# Probe-Scope_Power_v1_0.net
KiCad netlist of a schematic drawn in Altium Designer
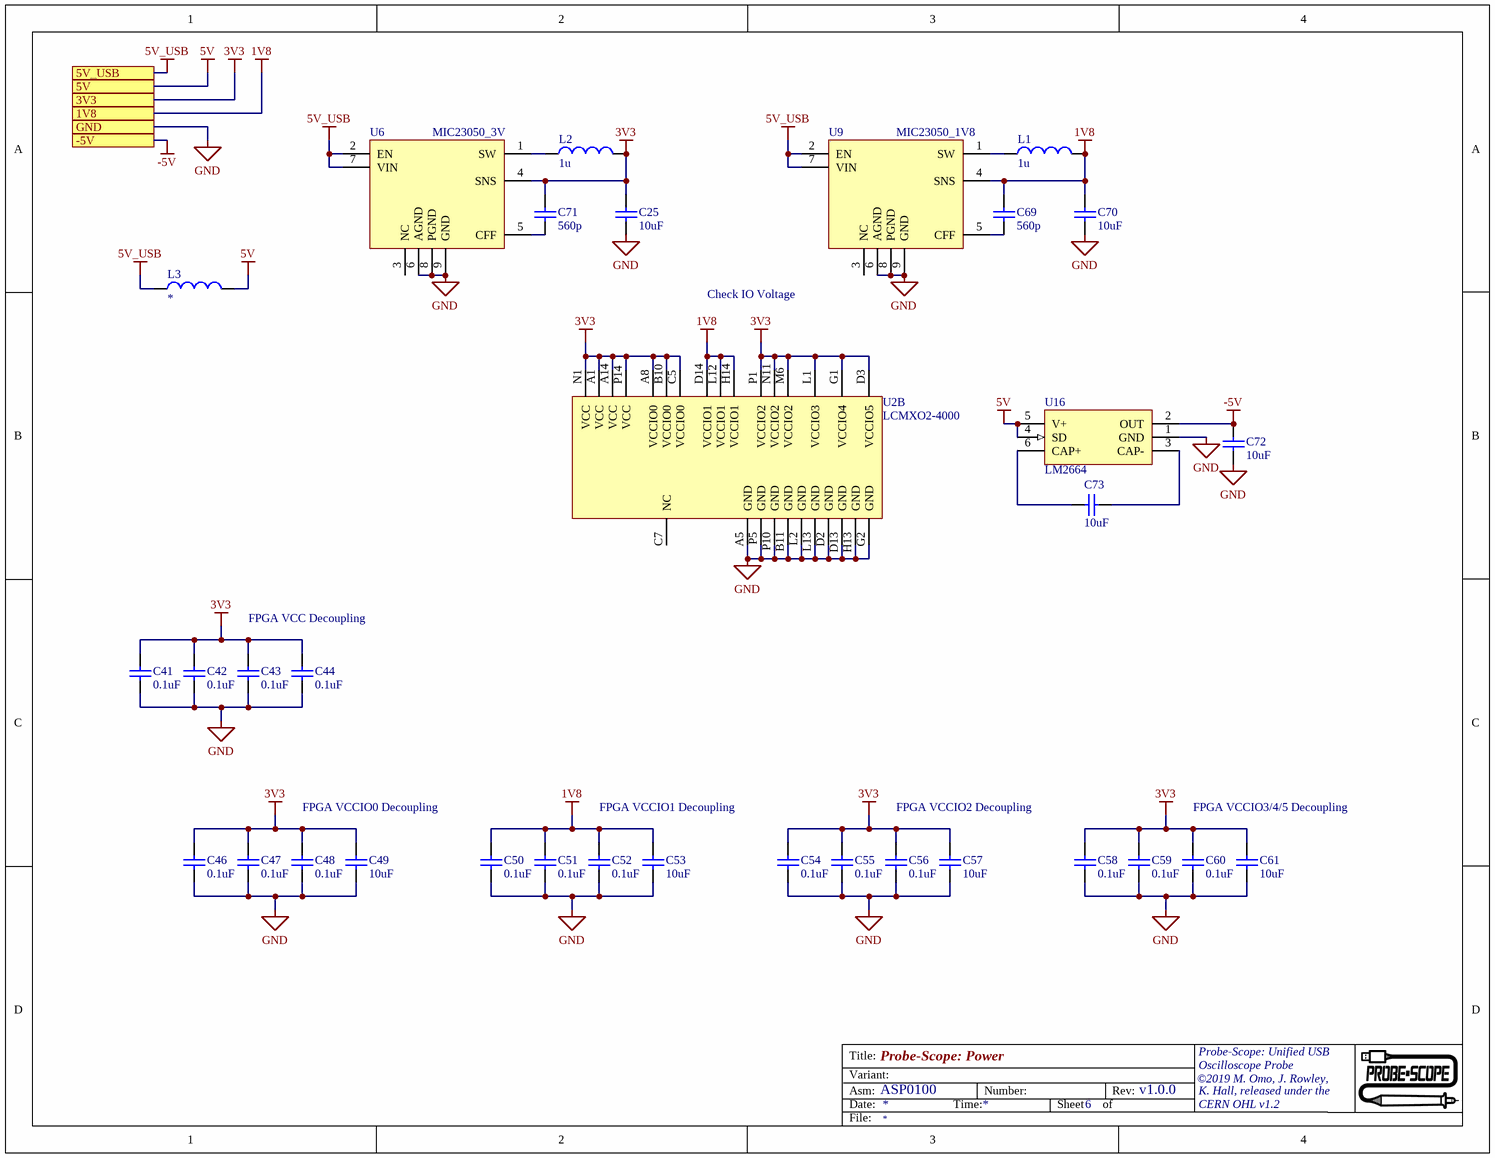
[diagram p0: Probe-Scope Power v1.0.SchDoc]

(export (version "E")
  (design (tool "Eeschema 10.0.6"))
  (components
    (comp (ref "C25")
      (value "10uF")
      (footprint "0603(1608)")
      (fields
        (field (name "MANF") "Samsung Electro-Mechanics")
        (field (name "TOLERANCE") "20")
        (field (name "VOLTAGE") "25")
        (field (name "MODIFIED BY") "sotterbacher")
        (field (name "APPROVED") "True")
      )
      (libsource (lib "MENG Database Library VPN") (part "Cap"))
    )
    (comp (ref "C41")
      (value "0.1uF")
      (footprint "0402(1005)")
      (fields
        (field (name "MANF") "Samsung Electro-Mechanics")
        (field (name "TOLERANCE") "10")
        (field (name "VOLTAGE") "6.3")
        (field (name "MODIFIED BY") "jrowley")
        (field (name "APPROVED") "False")
      )
      (libsource (lib "MENG Database Library VPN") (part "Cap"))
    )
    (comp (ref "C42")
      (value "0.1uF")
      (footprint "0402(1005)")
      (fields
        (field (name "MANF") "Samsung Electro-Mechanics")
        (field (name "TOLERANCE") "10")
        (field (name "VOLTAGE") "6.3")
        (field (name "MODIFIED BY") "jrowley")
        (field (name "APPROVED") "False")
      )
      (libsource (lib "MENG Database Library VPN") (part "Cap"))
    )
    (comp (ref "C43")
      (value "0.1uF")
      (footprint "0402(1005)")
      (fields
        (field (name "MANF") "Samsung Electro-Mechanics")
        (field (name "TOLERANCE") "10")
        (field (name "VOLTAGE") "6.3")
        (field (name "MODIFIED BY") "jrowley")
        (field (name "APPROVED") "False")
      )
      (libsource (lib "MENG Database Library VPN") (part "Cap"))
    )
    (comp (ref "C44")
      (value "0.1uF")
      (footprint "0402(1005)")
      (fields
        (field (name "MANF") "Samsung Electro-Mechanics")
        (field (name "TOLERANCE") "10")
        (field (name "VOLTAGE") "6.3")
        (field (name "MODIFIED BY") "jrowley")
        (field (name "APPROVED") "False")
      )
      (libsource (lib "MENG Database Library VPN") (part "Cap"))
    )
    (comp (ref "C46")
      (value "0.1uF")
      (footprint "0402(1005)")
      (fields
        (field (name "MANF") "Samsung Electro-Mechanics")
        (field (name "TOLERANCE") "10")
        (field (name "VOLTAGE") "6.3")
        (field (name "MODIFIED BY") "jrowley")
        (field (name "APPROVED") "False")
      )
      (libsource (lib "MENG Database Library VPN") (part "Cap"))
    )
    (comp (ref "C47")
      (value "0.1uF")
      (footprint "0402(1005)")
      (fields
        (field (name "MANF") "Samsung Electro-Mechanics")
        (field (name "TOLERANCE") "10")
        (field (name "VOLTAGE") "6.3")
        (field (name "MODIFIED BY") "jrowley")
        (field (name "APPROVED") "False")
      )
      (libsource (lib "MENG Database Library VPN") (part "Cap"))
    )
    (comp (ref "C48")
      (value "0.1uF")
      (footprint "0402(1005)")
      (fields
        (field (name "MANF") "Samsung Electro-Mechanics")
        (field (name "TOLERANCE") "10")
        (field (name "VOLTAGE") "6.3")
        (field (name "MODIFIED BY") "jrowley")
        (field (name "APPROVED") "False")
      )
      (libsource (lib "MENG Database Library VPN") (part "Cap"))
    )
    (comp (ref "C49")
      (value "10uF")
      (footprint "0603(1608)")
      (fields
        (field (name "MANF") "Samsung Electro-Mechanics")
        (field (name "TOLERANCE") "20")
        (field (name "VOLTAGE") "25")
        (field (name "MODIFIED BY") "sotterbacher")
        (field (name "APPROVED") "True")
      )
      (libsource (lib "MENG Database Library VPN") (part "Cap"))
    )
    (comp (ref "C50")
      (value "0.1uF")
      (footprint "0402(1005)")
      (fields
        (field (name "MANF") "Samsung Electro-Mechanics")
        (field (name "TOLERANCE") "10")
        (field (name "VOLTAGE") "6.3")
        (field (name "MODIFIED BY") "jrowley")
        (field (name "APPROVED") "False")
      )
      (libsource (lib "MENG Database Library VPN") (part "Cap"))
    )
    (comp (ref "C51")
      (value "0.1uF")
      (footprint "0402(1005)")
      (fields
        (field (name "MANF") "Samsung Electro-Mechanics")
        (field (name "TOLERANCE") "10")
        (field (name "VOLTAGE") "6.3")
        (field (name "MODIFIED BY") "jrowley")
        (field (name "APPROVED") "False")
      )
      (libsource (lib "MENG Database Library VPN") (part "Cap"))
    )
    (comp (ref "C52")
      (value "0.1uF")
      (footprint "0402(1005)")
      (fields
        (field (name "MANF") "Samsung Electro-Mechanics")
        (field (name "TOLERANCE") "10")
        (field (name "VOLTAGE") "6.3")
        (field (name "MODIFIED BY") "jrowley")
        (field (name "APPROVED") "False")
      )
      (libsource (lib "MENG Database Library VPN") (part "Cap"))
    )
    (comp (ref "C53")
      (value "10uF")
      (footprint "0603(1608)")
      (fields
        (field (name "MANF") "Samsung Electro-Mechanics")
        (field (name "TOLERANCE") "20")
        (field (name "VOLTAGE") "25")
        (field (name "MODIFIED BY") "sotterbacher")
        (field (name "APPROVED") "True")
      )
      (libsource (lib "MENG Database Library VPN") (part "Cap"))
    )
    (comp (ref "C54")
      (value "0.1uF")
      (footprint "0402(1005)")
      (fields
        (field (name "MANF") "Samsung Electro-Mechanics")
        (field (name "TOLERANCE") "10")
        (field (name "VOLTAGE") "6.3")
        (field (name "MODIFIED BY") "jrowley")
        (field (name "APPROVED") "False")
      )
      (libsource (lib "MENG Database Library VPN") (part "Cap"))
    )
    (comp (ref "C55")
      (value "0.1uF")
      (footprint "0402(1005)")
      (fields
        (field (name "MANF") "Samsung Electro-Mechanics")
        (field (name "TOLERANCE") "10")
        (field (name "VOLTAGE") "6.3")
        (field (name "MODIFIED BY") "jrowley")
        (field (name "APPROVED") "False")
      )
      (libsource (lib "MENG Database Library VPN") (part "Cap"))
    )
    (comp (ref "C56")
      (value "0.1uF")
      (footprint "0402(1005)")
      (fields
        (field (name "MANF") "Samsung Electro-Mechanics")
        (field (name "TOLERANCE") "10")
        (field (name "VOLTAGE") "6.3")
        (field (name "MODIFIED BY") "jrowley")
        (field (name "APPROVED") "False")
      )
      (libsource (lib "MENG Database Library VPN") (part "Cap"))
    )
    (comp (ref "C57")
      (value "10uF")
      (footprint "0603(1608)")
      (fields
        (field (name "MANF") "Samsung Electro-Mechanics")
        (field (name "TOLERANCE") "20")
        (field (name "VOLTAGE") "25")
        (field (name "MODIFIED BY") "sotterbacher")
        (field (name "APPROVED") "True")
      )
      (libsource (lib "MENG Database Library VPN") (part "Cap"))
    )
    (comp (ref "C58")
      (value "0.1uF")
      (footprint "0402(1005)")
      (fields
        (field (name "MANF") "Samsung Electro-Mechanics")
        (field (name "TOLERANCE") "10")
        (field (name "VOLTAGE") "6.3")
        (field (name "MODIFIED BY") "jrowley")
        (field (name "APPROVED") "False")
      )
      (libsource (lib "MENG Database Library VPN") (part "Cap"))
    )
    (comp (ref "C59")
      (value "0.1uF")
      (footprint "0402(1005)")
      (fields
        (field (name "MANF") "Samsung Electro-Mechanics")
        (field (name "TOLERANCE") "10")
        (field (name "VOLTAGE") "6.3")
        (field (name "MODIFIED BY") "jrowley")
        (field (name "APPROVED") "False")
      )
      (libsource (lib "MENG Database Library VPN") (part "Cap"))
    )
    (comp (ref "C60")
      (value "0.1uF")
      (footprint "0402(1005)")
      (fields
        (field (name "MANF") "Samsung Electro-Mechanics")
        (field (name "TOLERANCE") "10")
        (field (name "VOLTAGE") "6.3")
        (field (name "MODIFIED BY") "jrowley")
        (field (name "APPROVED") "False")
      )
      (libsource (lib "MENG Database Library VPN") (part "Cap"))
    )
    (comp (ref "C61")
      (value "10uF")
      (footprint "0603(1608)")
      (fields
        (field (name "MANF") "Samsung Electro-Mechanics")
        (field (name "TOLERANCE") "20")
        (field (name "VOLTAGE") "25")
        (field (name "MODIFIED BY") "sotterbacher")
        (field (name "APPROVED") "True")
      )
      (libsource (lib "MENG Database Library VPN") (part "Cap"))
    )
    (comp (ref "C69")
      (value "560p")
      (footprint "0402(1005)")
      (fields
        (field (name "MANF") "Samsung Electro-Mechanics")
        (field (name "TOLERANCE") "10")
        (field (name "VOLTAGE") "50")
        (field (name "MODIFIED BY") "momo")
        (field (name "APPROVED") "False")
      )
      (libsource (lib "MENG Database Library 18") (part "Cap"))
    )
    (comp (ref "C70")
      (value "10uF")
      (footprint "0603(1608)")
      (fields
        (field (name "MANF") "Samsung Electro-Mechanics")
        (field (name "TOLERANCE") "20")
        (field (name "VOLTAGE") "25")
        (field (name "MODIFIED BY") "sotterbacher")
        (field (name "APPROVED") "True")
      )
      (libsource (lib "MENG Database Library VPN") (part "Cap"))
    )
    (comp (ref "C71")
      (value "560p")
      (footprint "0402(1005)")
      (fields
        (field (name "MANF") "Samsung Electro-Mechanics")
        (field (name "TOLERANCE") "10")
        (field (name "VOLTAGE") "50")
        (field (name "MODIFIED BY") "momo")
        (field (name "APPROVED") "False")
      )
      (libsource (lib "MENG Database Library 18") (part "Cap"))
    )
    (comp (ref "C72")
      (value "10uF")
      (footprint "0603(1608)")
      (fields
        (field (name "MANF") "Samsung Electro-Mechanics")
        (field (name "TOLERANCE") "20")
        (field (name "VOLTAGE") "25")
        (field (name "MODIFIED BY") "sotterbacher")
        (field (name "APPROVED") "True")
      )
      (libsource (lib "MENG Database Library VPN") (part "Cap"))
    )
    (comp (ref "C73")
      (value "10uF")
      (footprint "0603(1608)")
      (fields
        (field (name "MANF") "Samsung Electro-Mechanics")
        (field (name "TOLERANCE") "20")
        (field (name "VOLTAGE") "25")
        (field (name "MODIFIED BY") "sotterbacher")
        (field (name "APPROVED") "True")
      )
      (libsource (lib "MENG Database Library VPN") (part "Cap"))
    )
    (comp (ref "L1")
      (value "1u")
      (footprint "0603(1608)")
      (fields
        (field (name "MANF") "Taiyo Yuden")
        (field (name "TOLERANCE") "20")
        (field (name "Comment") "Inductor")
        (field (name "MODIFIED BY") "momo")
        (field (name "APPROVED") "False")
      )
      (libsource (lib "MENG Database Library 18") (part "Inductor"))
    )
    (comp (ref "L2")
      (value "1u")
      (footprint "0603(1608)")
      (fields
        (field (name "MANF") "Taiyo Yuden")
        (field (name "TOLERANCE") "20")
        (field (name "Comment") "Inductor")
        (field (name "MODIFIED BY") "momo")
        (field (name "APPROVED") "False")
      )
      (libsource (lib "MENG Database Library 18") (part "Inductor"))
    )
    (comp (ref "L3")
      (value "Ferrite Bead Y")
      (footprint "0805(2012)")
      (fields
        (field (name "ALTIUM_VALUE") "*")
        (field (name "MANF") "TDK")
        (field (name "MODIFIED BY") "pmarcus")
        (field (name "APPROVED") "True")
      )
      (libsource (lib "MENG Database Library 18") (part "Inductor"))
    )
    (comp (ref "U2")
      (value "LCMXO2-4000")
      (footprint "132_Ball_csBGA_MachXO2")
      (fields (field (name "MANF") "Lattice Semiconductor"))
      (libsource (lib "PS v1.0") (part "MachXO2-4000"))
    )
    (comp (ref "U6")
      (value "MIC23050_3V")
      (footprint "MCP_8_MLF")
      (fields (field (name "MANF") "Microchip"))
      (libsource (lib "PS v1.0") (part "MIC23050_3V"))
    )
    (comp (ref "U9")
      (value "MIC23050_1V8")
      (footprint "MCP_8_MLF")
      (fields (field (name "MANF") "Microchip"))
      (libsource (lib "PS v1.0") (part "MIC23050_1V8"))
    )
    (comp (ref "U16")
      (value "LM2664")
      (footprint "SOT95P280X145-6N")
      (fields (field (name "MANF") "Texas Instruments"))
      (libsource (lib "PS v1.0") (part "LM2664"))
    )
  )
  (nets
    (net (code "1") (name "-5V") (class "Default")
      (node (ref "C72") (pin "2") (pinfunction "2_2") (pintype "passive"))
      (node (ref "U16") (pin "2") (pinfunction "OUT_2") (pintype "power_in"))
    )
    (net (code "2") (name "1V8") (class "Default")
      (node (ref "C50") (pin "2") (pinfunction "2_2") (pintype "passive"))
      (node (ref "C51") (pin "2") (pinfunction "2_2") (pintype "passive"))
      (node (ref "C52") (pin "2") (pinfunction "2_2") (pintype "passive"))
      (node (ref "C53") (pin "2") (pinfunction "2_2") (pintype "passive"))
      (node (ref "C69") (pin "2") (pinfunction "2_2") (pintype "passive"))
      (node (ref "C70") (pin "2") (pinfunction "2_2") (pintype "passive"))
      (node (ref "L1") (pin "2") (pinfunction "2_2") (pintype "passive"))
      (node (ref "U2") (pin "D14") (pinfunction "VCCIO1_D14") (pintype "power_in"))
      (node (ref "U2") (pin "H14") (pinfunction "VCCIO1_H14") (pintype "power_in"))
      (node (ref "U2") (pin "L12") (pinfunction "VCCIO1_L12") (pintype "power_in"))
      (node (ref "U9") (pin "4") (pinfunction "SNS_4") (pintype "passive"))
    )
    (net (code "3") (name "3V3") (class "Default")
      (node (ref "C25") (pin "2") (pinfunction "2_2") (pintype "passive"))
      (node (ref "C41") (pin "2") (pinfunction "2_2") (pintype "passive"))
      (node (ref "C42") (pin "2") (pinfunction "2_2") (pintype "passive"))
      (node (ref "C43") (pin "2") (pinfunction "2_2") (pintype "passive"))
      (node (ref "C44") (pin "2") (pinfunction "2_2") (pintype "passive"))
      (node (ref "C46") (pin "2") (pinfunction "2_2") (pintype "passive"))
      (node (ref "C47") (pin "2") (pinfunction "2_2") (pintype "passive"))
      (node (ref "C48") (pin "2") (pinfunction "2_2") (pintype "passive"))
      (node (ref "C49") (pin "2") (pinfunction "2_2") (pintype "passive"))
      (node (ref "C54") (pin "2") (pinfunction "2_2") (pintype "passive"))
      (node (ref "C55") (pin "2") (pinfunction "2_2") (pintype "passive"))
      (node (ref "C56") (pin "2") (pinfunction "2_2") (pintype "passive"))
      (node (ref "C57") (pin "2") (pinfunction "2_2") (pintype "passive"))
      (node (ref "C58") (pin "2") (pinfunction "2_2") (pintype "passive"))
      (node (ref "C59") (pin "2") (pinfunction "2_2") (pintype "passive"))
      (node (ref "C60") (pin "2") (pinfunction "2_2") (pintype "passive"))
      (node (ref "C61") (pin "2") (pinfunction "2_2") (pintype "passive"))
      (node (ref "C71") (pin "2") (pinfunction "2_2") (pintype "passive"))
      (node (ref "L2") (pin "2") (pinfunction "2_2") (pintype "passive"))
      (node (ref "U2") (pin "A1") (pinfunction "VCC_A1") (pintype "power_in"))
      (node (ref "U2") (pin "A14") (pinfunction "VCC_A14") (pintype "power_in"))
      (node (ref "U2") (pin "A8") (pinfunction "VCCIO0_A8") (pintype "power_in"))
      (node (ref "U2") (pin "B10") (pinfunction "VCCIO0_B10") (pintype "power_in"))
      (node (ref "U2") (pin "C5") (pinfunction "VCCIO0_C5") (pintype "power_in"))
      (node (ref "U2") (pin "D3") (pinfunction "VCCIO5_D3") (pintype "power_in"))
      (node (ref "U2") (pin "G1") (pinfunction "VCCIO4_G1") (pintype "power_in"))
      (node (ref "U2") (pin "L1") (pinfunction "VCCIO3_L1") (pintype "power_in"))
      (node (ref "U2") (pin "M6") (pinfunction "VCCIO2_M6") (pintype "power_in"))
      (node (ref "U2") (pin "N1") (pinfunction "VCC_N1") (pintype "power_in"))
      (node (ref "U2") (pin "N11") (pinfunction "VCCIO2_N11") (pintype "power_in"))
      (node (ref "U2") (pin "P1") (pinfunction "VCCIO2_P1") (pintype "power_in"))
      (node (ref "U2") (pin "P14") (pinfunction "VCC_P14") (pintype "power_in"))
      (node (ref "U6") (pin "4") (pinfunction "SNS_4") (pintype "passive"))
    )
    (net (code "4") (name "5V") (class "Default")
      (node (ref "L3") (pin "2") (pinfunction "2_2") (pintype "passive"))
      (node (ref "U16") (pin "4") (pinfunction "SD_4") (pintype "input"))
      (node (ref "U16") (pin "5") (pinfunction "V+_5") (pintype "power_in"))
    )
    (net (code "5") (name "5V_USB") (class "Default")
      (node (ref "L3") (pin "1") (pinfunction "1_1") (pintype "passive"))
      (node (ref "U6") (pin "2") (pinfunction "EN_2") (pintype "passive"))
      (node (ref "U6") (pin "7") (pinfunction "VIN_7") (pintype "passive"))
      (node (ref "U9") (pin "2") (pinfunction "EN_2") (pintype "passive"))
      (node (ref "U9") (pin "7") (pinfunction "VIN_7") (pintype "passive"))
    )
    (net (code "6") (name "GND") (class "Default")
      (node (ref "C25") (pin "1") (pinfunction "1_1") (pintype "passive"))
      (node (ref "C41") (pin "1") (pinfunction "1_1") (pintype "passive"))
      (node (ref "C42") (pin "1") (pinfunction "1_1") (pintype "passive"))
      (node (ref "C43") (pin "1") (pinfunction "1_1") (pintype "passive"))
      (node (ref "C44") (pin "1") (pinfunction "1_1") (pintype "passive"))
      (node (ref "C46") (pin "1") (pinfunction "1_1") (pintype "passive"))
      (node (ref "C47") (pin "1") (pinfunction "1_1") (pintype "passive"))
      (node (ref "C48") (pin "1") (pinfunction "1_1") (pintype "passive"))
      (node (ref "C49") (pin "1") (pinfunction "1_1") (pintype "passive"))
      (node (ref "C50") (pin "1") (pinfunction "1_1") (pintype "passive"))
      (node (ref "C51") (pin "1") (pinfunction "1_1") (pintype "passive"))
      (node (ref "C52") (pin "1") (pinfunction "1_1") (pintype "passive"))
      (node (ref "C53") (pin "1") (pinfunction "1_1") (pintype "passive"))
      (node (ref "C54") (pin "1") (pinfunction "1_1") (pintype "passive"))
      (node (ref "C55") (pin "1") (pinfunction "1_1") (pintype "passive"))
      (node (ref "C56") (pin "1") (pinfunction "1_1") (pintype "passive"))
      (node (ref "C57") (pin "1") (pinfunction "1_1") (pintype "passive"))
      (node (ref "C58") (pin "1") (pinfunction "1_1") (pintype "passive"))
      (node (ref "C59") (pin "1") (pinfunction "1_1") (pintype "passive"))
      (node (ref "C60") (pin "1") (pinfunction "1_1") (pintype "passive"))
      (node (ref "C61") (pin "1") (pinfunction "1_1") (pintype "passive"))
      (node (ref "C70") (pin "1") (pinfunction "1_1") (pintype "passive"))
      (node (ref "C72") (pin "1") (pinfunction "1_1") (pintype "passive"))
      (node (ref "U16") (pin "1") (pinfunction "GND_1") (pintype "power_in"))
      (node (ref "U2") (pin "A5") (pinfunction "GND_A5") (pintype "power_in"))
      (node (ref "U2") (pin "B11") (pinfunction "GND_B11") (pintype "power_in"))
      (node (ref "U2") (pin "D13") (pinfunction "GND_D13") (pintype "power_in"))
      (node (ref "U2") (pin "D2") (pinfunction "GND_D2") (pintype "power_in"))
      (node (ref "U2") (pin "G2") (pinfunction "GND_G2") (pintype "power_in"))
      (node (ref "U2") (pin "H13") (pinfunction "GND_H13") (pintype "power_in"))
      (node (ref "U2") (pin "L13") (pinfunction "GND_L13") (pintype "power_in"))
      (node (ref "U2") (pin "L2") (pinfunction "GND_L2") (pintype "power_in"))
      (node (ref "U2") (pin "P10") (pinfunction "GND_P10") (pintype "power_in"))
      (node (ref "U2") (pin "P5") (pinfunction "GND_P5") (pintype "power_in"))
      (node (ref "U6") (pin "6") (pinfunction "AGND_6") (pintype "passive"))
      (node (ref "U6") (pin "8") (pinfunction "PGND_8") (pintype "passive"))
      (node (ref "U6") (pin "9") (pinfunction "GND_9") (pintype "passive"))
      (node (ref "U9") (pin "6") (pinfunction "AGND_6") (pintype "passive"))
      (node (ref "U9") (pin "8") (pinfunction "PGND_8") (pintype "passive"))
      (node (ref "U9") (pin "9") (pinfunction "GND_9") (pintype "passive"))
    )
    (net (code "7") (name "Net-(U6-CFF)") (class "Default")
      (node (ref "C71") (pin "1") (pinfunction "1_1") (pintype "passive"))
      (node (ref "U6") (pin "5") (pinfunction "CFF_5") (pintype "passive"))
    )
    (net (code "8") (name "Net-(U6-SW)") (class "Default")
      (node (ref "L2") (pin "1") (pinfunction "1_1") (pintype "passive"))
      (node (ref "U6") (pin "1") (pinfunction "SW_1") (pintype "passive"))
    )
    (net (code "9") (name "Net-(U9-CFF)") (class "Default")
      (node (ref "C69") (pin "1") (pinfunction "1_1") (pintype "passive"))
      (node (ref "U9") (pin "5") (pinfunction "CFF_5") (pintype "passive"))
    )
    (net (code "10") (name "Net-(U9-SW)") (class "Default")
      (node (ref "L1") (pin "1") (pinfunction "1_1") (pintype "passive"))
      (node (ref "U9") (pin "1") (pinfunction "SW_1") (pintype "passive"))
    )
    (net (code "11") (name "Net-(U16-CAP+)") (class "Default")
      (node (ref "C73") (pin "2") (pinfunction "2_2") (pintype "passive"))
      (node (ref "U16") (pin "6") (pinfunction "CAP+_6") (pintype "power_in"))
    )
    (net (code "12") (name "Net-(U16-CAP-)") (class "Default")
      (node (ref "C73") (pin "1") (pinfunction "1_1") (pintype "passive"))
      (node (ref "U16") (pin "3") (pinfunction "CAP-_3") (pintype "power_in"))
    )
    (net (code "13") (name "unconnected-(U2B-NC-PadC7)") (class "Default")
      (node (ref "U2") (pin "C7") (pinfunction "NC_C7") (pintype "power_in"))
    )
    (net (code "14") (name "unconnected-(U6-NC-Pad3)") (class "Default")
      (node (ref "U6") (pin "3") (pinfunction "NC_3") (pintype "passive"))
    )
    (net (code "15") (name "unconnected-(U9-NC-Pad3)") (class "Default")
      (node (ref "U9") (pin "3") (pinfunction "NC_3") (pintype "passive"))
    )
  )
)
